# LightSwitch.net
KiCad netlist of a schematic drawn in EAGLE
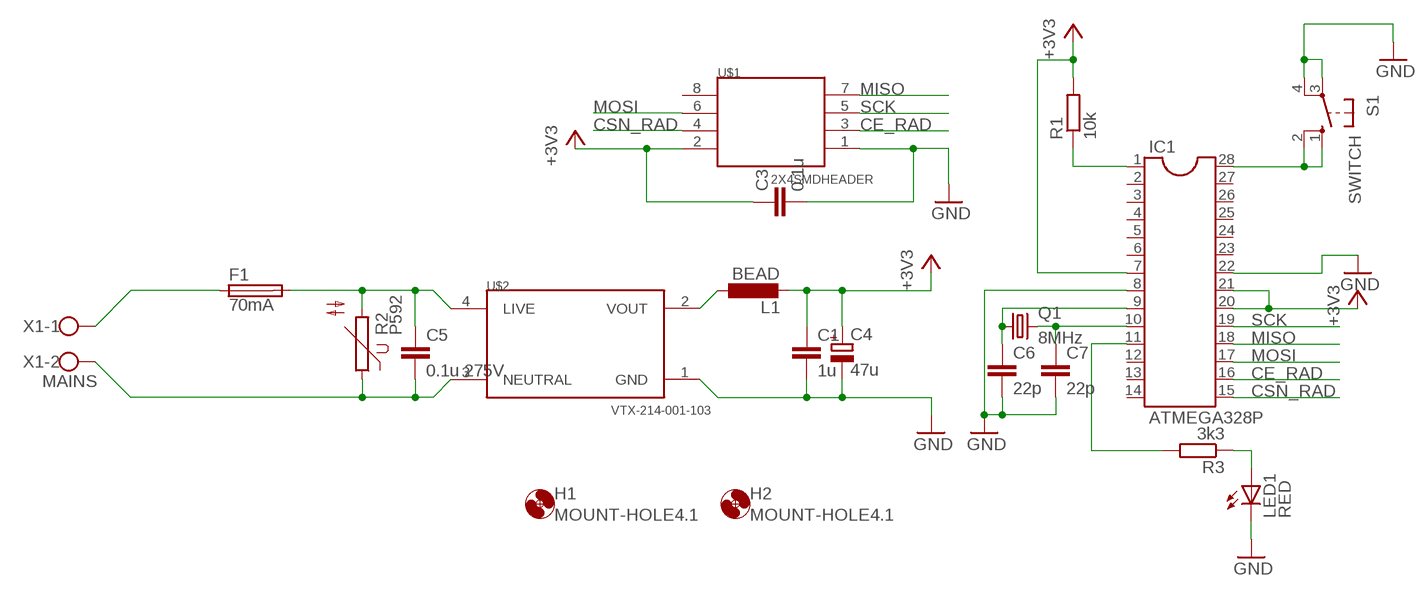
[diagram p0: schematic, sheet 1]

(export (version "E")
  (design (tool "Eeschema 10.0.6"))
  (components
    (comp (ref "C1")
      (value "1u")
      (footprint "eagle-import:C1206K")
      (libsource (lib "eagle-import") (part "C-EUC1206K"))
    )
    (comp (ref "C3")
      (value "0.1u")
      (footprint "eagle-import:C1206")
      (libsource (lib "eagle-import") (part "C-EUC1206"))
    )
    (comp (ref "C4")
      (value "47u")
      (footprint "eagle-import:E2,5-6E")
      (libsource (lib "eagle-import") (part "CPOL-EUE2,5-6E"))
    )
    (comp (ref "C5")
      (value "0.1u 275V")
      (footprint "eagle-import:C15B5")
      (libsource (lib "eagle-import") (part "C15/5"))
    )
    (comp (ref "C6")
      (value "22p")
      (footprint "eagle-import:C1206")
      (libsource (lib "eagle-import") (part "C-EUC1206"))
    )
    (comp (ref "C7")
      (value "22p")
      (footprint "eagle-import:C1206")
      (libsource (lib "eagle-import") (part "C-EUC1206"))
    )
    (comp (ref "F1")
      (value "70mA")
      (footprint "eagle-import:SH22,5A")
      (libsource (lib "eagle-import") (part "FUSESH22,5A"))
    )
    (comp (ref "H1")
      (value "MOUNT-HOLE4.1")
      (footprint "eagle-import:4,1")
      (libsource (lib "eagle-import") (part "MOUNT-HOLE4.1"))
    )
    (comp (ref "H2")
      (value "MOUNT-HOLE4.1")
      (footprint "eagle-import:4,1")
      (libsource (lib "eagle-import") (part "MOUNT-HOLE4.1"))
    )
    (comp (ref "IC1")
      (value "ATMEGA328P")
      (footprint "eagle-import:DIL28-3")
      (libsource (lib "eagle-import") (part "DIL28-3"))
    )
    (comp (ref "L1")
      (value "BEAD")
      (footprint "eagle-import:L3230M")
      (libsource (lib "eagle-import") (part "L-EUL3230M"))
    )
    (comp (ref "LED1")
      (value "RED")
      (footprint "eagle-import:LED5MM")
      (libsource (lib "eagle-import") (part "LED5MM"))
    )
    (comp (ref "Q1")
      (value "8MHz")
      (footprint "eagle-import:HC49U70")
      (libsource (lib "eagle-import") (part "CRYSTALHC49U70"))
    )
    (comp (ref "R1")
      (value "10k")
      (footprint "eagle-import:R1206")
      (libsource (lib "eagle-import") (part "R-EU_R1206"))
    )
    (comp (ref "R2")
      (value "P592")
      (footprint "eagle-import:P592")
      (libsource (lib "eagle-import") (part "P592"))
    )
    (comp (ref "R3")
      (value "3k3")
      (footprint "eagle-import:R1206")
      (libsource (lib "eagle-import") (part "R-EU_R1206"))
    )
    (comp (ref "S1")
      (value "SWITCH")
      (footprint "eagle-import:B3F-40XX")
      (fields (field (name "MF") "OMRON COMPONENTS USA") (field (name "MPN") "B3F-4000"))
      (libsource (lib "eagle-import") (part "40-XX"))
    )
    (comp (ref "U$1")
      (value "2X4SMDHEADER")
      (footprint "eagle-import:TSM-110-XX-XXX-DV")
      (libsource (lib "eagle-import") (part "2X4SMDHEADER"))
    )
    (comp (ref "U$2")
      (value "VTX-214-001-103")
      (footprint "eagle-import:VTX214001103")
      (libsource (lib "eagle-import") (part "VTX-214-001-103"))
    )
    (comp (ref "X1")
      (value "MAINS")
      (footprint "eagle-import:W237-102")
      (fields (field (name "MPN") "237-102"))
      (libsource (lib "eagle-import") (part "W237-102"))
    )
  )
  (nets
    (net (code "1") (name "+3V3") (class "Default")
      (node (ref "C1") (pin "1") (pinfunction "1_1") (pintype "passive"))
      (node (ref "C3") (pin "1") (pinfunction "1_1") (pintype "passive"))
      (node (ref "C4") (pin "+") (pinfunction "+_+") (pintype "passive"))
      (node (ref "IC1") (pin "20") (pinfunction "20_20") (pintype "passive"))
      (node (ref "IC1") (pin "21") (pinfunction "21_21") (pintype "passive"))
      (node (ref "IC1") (pin "7") (pinfunction "7_7") (pintype "passive"))
      (node (ref "L1") (pin "2") (pinfunction "2_2") (pintype "passive"))
      (node (ref "R1") (pin "2") (pinfunction "2_2") (pintype "passive"))
      (node (ref "U$1") (pin "2") (pinfunction "2_2") (pintype "bidirectional"))
    )
    (net (code "2") (name "/CE_RAD") (class "Default")
      (node (ref "IC1") (pin "16") (pinfunction "16_16") (pintype "passive"))
      (node (ref "U$1") (pin "3") (pinfunction "3_3") (pintype "bidirectional"))
    )
    (net (code "3") (name "/CSN_RAD") (class "Default")
      (node (ref "IC1") (pin "15") (pinfunction "15_15") (pintype "passive"))
      (node (ref "U$1") (pin "4") (pinfunction "4_4") (pintype "bidirectional"))
    )
    (net (code "4") (name "/MISO") (class "Default")
      (node (ref "IC1") (pin "18") (pinfunction "18_18") (pintype "passive"))
      (node (ref "U$1") (pin "7") (pinfunction "7_7") (pintype "bidirectional"))
    )
    (net (code "5") (name "/MOSI") (class "Default")
      (node (ref "IC1") (pin "17") (pinfunction "17_17") (pintype "passive"))
      (node (ref "U$1") (pin "6") (pinfunction "6_6") (pintype "bidirectional"))
    )
    (net (code "6") (name "/SCK") (class "Default")
      (node (ref "IC1") (pin "19") (pinfunction "19_19") (pintype "passive"))
      (node (ref "U$1") (pin "5") (pinfunction "5_5") (pintype "bidirectional"))
    )
    (net (code "7") (name "GND") (class "Default")
      (node (ref "C1") (pin "2") (pinfunction "2_2") (pintype "passive"))
      (node (ref "C3") (pin "2") (pinfunction "2_2") (pintype "passive"))
      (node (ref "C4") (pin "-") (pinfunction "-_-") (pintype "passive"))
      (node (ref "C6") (pin "2") (pinfunction "2_2") (pintype "passive"))
      (node (ref "C7") (pin "2") (pinfunction "2_2") (pintype "passive"))
      (node (ref "IC1") (pin "22") (pinfunction "22_22") (pintype "passive"))
      (node (ref "IC1") (pin "8") (pinfunction "8_8") (pintype "passive"))
      (node (ref "LED1") (pin "K") (pinfunction "C_K") (pintype "passive"))
      (node (ref "S1") (pin "3") (pinfunction "P_3") (pintype "passive"))
      (node (ref "S1") (pin "4") (pinfunction "P1_4") (pintype "passive"))
      (node (ref "U$1") (pin "1") (pinfunction "1_1") (pintype "bidirectional"))
      (node (ref "U$2") (pin "1") (pinfunction "GND_1") (pintype "power_in"))
    )
    (net (code "8") (name "Net-(C6-Pad1)") (class "Default")
      (node (ref "C6") (pin "1") (pinfunction "1_1") (pintype "passive"))
      (node (ref "IC1") (pin "9") (pinfunction "9_9") (pintype "passive"))
      (node (ref "Q1") (pin "1") (pinfunction "1_1") (pintype "passive"))
    )
    (net (code "9") (name "Net-(C7-Pad1)") (class "Default")
      (node (ref "C7") (pin "1") (pinfunction "1_1") (pintype "passive"))
      (node (ref "IC1") (pin "10") (pinfunction "10_10") (pintype "passive"))
      (node (ref "Q1") (pin "2") (pinfunction "2_2") (pintype "passive"))
    )
    (net (code "10") (name "Net-(IC1-Pad1)") (class "Default")
      (node (ref "IC1") (pin "1") (pinfunction "1_1") (pintype "passive"))
      (node (ref "R1") (pin "1") (pinfunction "1_1") (pintype "passive"))
    )
    (net (code "11") (name "Net-(IC1-Pad11)") (class "Default")
      (node (ref "IC1") (pin "11") (pinfunction "11_11") (pintype "passive"))
      (node (ref "R3") (pin "2") (pinfunction "2_2") (pintype "passive"))
    )
    (net (code "12") (name "Net-(LED1-PadA)") (class "Default")
      (node (ref "LED1") (pin "A") (pinfunction "A_A") (pintype "passive"))
      (node (ref "R3") (pin "1") (pinfunction "1_1") (pintype "passive"))
    )
    (net (code "13") (name "Net-(S1-S)") (class "Default")
      (node (ref "IC1") (pin "28") (pinfunction "28_28") (pintype "passive"))
      (node (ref "S1") (pin "1") (pinfunction "S_1") (pintype "passive"))
      (node (ref "S1") (pin "2") (pinfunction "S1_2") (pintype "passive"))
    )
    (net (code "14") (name "Net-(U$2-LIVE)") (class "Default")
      (node (ref "C5") (pin "1") (pinfunction "1_1") (pintype "passive"))
      (node (ref "F1") (pin "2") (pinfunction "2_2") (pintype "passive"))
      (node (ref "R2") (pin "2") (pinfunction "2_2") (pintype "passive"))
      (node (ref "U$2") (pin "4") (pinfunction "LIVE_4") (pintype "input"))
    )
    (net (code "15") (name "Net-(U$2-NEUTRAL)") (class "Default")
      (node (ref "C5") (pin "2") (pinfunction "2_2") (pintype "passive"))
      (node (ref "R2") (pin "1") (pinfunction "1_1") (pintype "passive"))
      (node (ref "U$2") (pin "3") (pinfunction "NEUTRAL_3") (pintype "input"))
      (node (ref "X1") (pin "2") (pinfunction "KL_2") (pintype "passive"))
    )
    (net (code "16") (name "Net-(U$2-VOUT)") (class "Default")
      (node (ref "L1") (pin "1") (pinfunction "1_1") (pintype "passive"))
      (node (ref "U$2") (pin "2") (pinfunction "VOUT_2") (pintype "power_in"))
    )
    (net (code "17") (name "Net-(X1A-KL)") (class "Default")
      (node (ref "F1") (pin "1") (pinfunction "1_1") (pintype "passive"))
      (node (ref "X1") (pin "1") (pinfunction "KL_1") (pintype "passive"))
    )
    (net (code "18") (name "unconnected-(IC1-Pad2)") (class "Default")
      (node (ref "IC1") (pin "2") (pinfunction "2_2") (pintype "passive"))
    )
    (net (code "19") (name "unconnected-(IC1-Pad3)") (class "Default")
      (node (ref "IC1") (pin "3") (pinfunction "3_3") (pintype "passive"))
    )
    (net (code "20") (name "unconnected-(IC1-Pad4)") (class "Default")
      (node (ref "IC1") (pin "4") (pinfunction "4_4") (pintype "passive"))
    )
    (net (code "21") (name "unconnected-(IC1-Pad5)") (class "Default")
      (node (ref "IC1") (pin "5") (pinfunction "5_5") (pintype "passive"))
    )
    (net (code "22") (name "unconnected-(IC1-Pad6)") (class "Default")
      (node (ref "IC1") (pin "6") (pinfunction "6_6") (pintype "passive"))
    )
    (net (code "23") (name "unconnected-(IC1-Pad12)") (class "Default")
      (node (ref "IC1") (pin "12") (pinfunction "12_12") (pintype "passive"))
    )
    (net (code "24") (name "unconnected-(IC1-Pad13)") (class "Default")
      (node (ref "IC1") (pin "13") (pinfunction "13_13") (pintype "passive"))
    )
    (net (code "25") (name "unconnected-(IC1-Pad14)") (class "Default")
      (node (ref "IC1") (pin "14") (pinfunction "14_14") (pintype "passive"))
    )
    (net (code "26") (name "unconnected-(IC1-Pad23)") (class "Default")
      (node (ref "IC1") (pin "23") (pinfunction "23_23") (pintype "passive"))
    )
    (net (code "27") (name "unconnected-(IC1-Pad24)") (class "Default")
      (node (ref "IC1") (pin "24") (pinfunction "24_24") (pintype "passive"))
    )
    (net (code "28") (name "unconnected-(IC1-Pad25)") (class "Default")
      (node (ref "IC1") (pin "25") (pinfunction "25_25") (pintype "passive"))
    )
    (net (code "29") (name "unconnected-(IC1-Pad26)") (class "Default")
      (node (ref "IC1") (pin "26") (pinfunction "26_26") (pintype "passive"))
    )
    (net (code "30") (name "unconnected-(IC1-Pad27)") (class "Default")
      (node (ref "IC1") (pin "27") (pinfunction "27_27") (pintype "passive"))
    )
    (net (code "31") (name "unconnected-(U$1-Pad8)") (class "Default")
      (node (ref "U$1") (pin "8") (pinfunction "8_8") (pintype "bidirectional"))
    )
  )
)
